# untitled.net
KiCad netlist of a schematic drawn in EAGLE
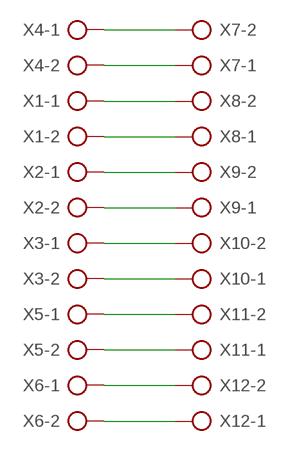
[diagram p0: schematic, sheet 1]

(export (version "E")
  (design (tool "Eeschema 10.0.6"))
  (components
    (comp (ref "X1")
      (value "AK500/2-H")
      (footprint "eagle-import:AK500_2-H")
      (libsource (lib "eagle-import") (part "AK500/2-H"))
    )
    (comp (ref "X2")
      (value "AK500/2-H")
      (footprint "eagle-import:AK500_2-H")
      (libsource (lib "eagle-import") (part "AK500/2-H"))
    )
    (comp (ref "X3")
      (value "AK500/2-H")
      (footprint "eagle-import:AK500_2-H")
      (libsource (lib "eagle-import") (part "AK500/2-H"))
    )
    (comp (ref "X4")
      (value "AK500/2-H")
      (footprint "eagle-import:AK500_2-H")
      (libsource (lib "eagle-import") (part "AK500/2-H"))
    )
    (comp (ref "X5")
      (value "AK500/2-H")
      (footprint "eagle-import:AK500_2-H")
      (libsource (lib "eagle-import") (part "AK500/2-H"))
    )
    (comp (ref "X6")
      (value "AK500/2-H")
      (footprint "eagle-import:AK500_2-H")
      (libsource (lib "eagle-import") (part "AK500/2-H"))
    )
    (comp (ref "X7")
      (value "AK500/2-H")
      (footprint "eagle-import:AK500_2-H")
      (libsource (lib "eagle-import") (part "AK500/2-H"))
    )
    (comp (ref "X8")
      (value "AK500/2-H")
      (footprint "eagle-import:AK500_2-H")
      (libsource (lib "eagle-import") (part "AK500/2-H"))
    )
    (comp (ref "X9")
      (value "AK500/2-H")
      (footprint "eagle-import:AK500_2-H")
      (libsource (lib "eagle-import") (part "AK500/2-H"))
    )
    (comp (ref "X10")
      (value "AK500/2-H")
      (footprint "eagle-import:AK500_2-H")
      (libsource (lib "eagle-import") (part "AK500/2-H"))
    )
    (comp (ref "X11")
      (value "AK500/2-H")
      (footprint "eagle-import:AK500_2-H")
      (libsource (lib "eagle-import") (part "AK500/2-H"))
    )
    (comp (ref "X12")
      (value "AK500/2-H")
      (footprint "eagle-import:AK500_2-H")
      (libsource (lib "eagle-import") (part "AK500/2-H"))
    )
  )
  (nets
    (net (code "1") (name "Net-(X1A-KL)") (class "Default")
      (node (ref "X1") (pin "1") (pinfunction "KL_1") (pintype "passive"))
      (node (ref "X8") (pin "2") (pinfunction "KL_2") (pintype "passive"))
    )
    (net (code "2") (name "Net-(X1B-KL)") (class "Default")
      (node (ref "X1") (pin "2") (pinfunction "KL_2") (pintype "passive"))
      (node (ref "X8") (pin "1") (pinfunction "KL_1") (pintype "passive"))
    )
    (net (code "3") (name "Net-(X2A-KL)") (class "Default")
      (node (ref "X2") (pin "1") (pinfunction "KL_1") (pintype "passive"))
      (node (ref "X9") (pin "2") (pinfunction "KL_2") (pintype "passive"))
    )
    (net (code "4") (name "Net-(X2B-KL)") (class "Default")
      (node (ref "X2") (pin "2") (pinfunction "KL_2") (pintype "passive"))
      (node (ref "X9") (pin "1") (pinfunction "KL_1") (pintype "passive"))
    )
    (net (code "5") (name "Net-(X4A-KL)") (class "Default")
      (node (ref "X4") (pin "1") (pinfunction "KL_1") (pintype "passive"))
      (node (ref "X7") (pin "2") (pinfunction "KL_2") (pintype "passive"))
    )
    (net (code "6") (name "Net-(X4B-KL)") (class "Default")
      (node (ref "X4") (pin "2") (pinfunction "KL_2") (pintype "passive"))
      (node (ref "X7") (pin "1") (pinfunction "KL_1") (pintype "passive"))
    )
    (net (code "7") (name "Net-(X10A-KL)") (class "Default")
      (node (ref "X10") (pin "1") (pinfunction "KL_1") (pintype "passive"))
      (node (ref "X3") (pin "2") (pinfunction "KL_2") (pintype "passive"))
    )
    (net (code "8") (name "Net-(X10B-KL)") (class "Default")
      (node (ref "X10") (pin "2") (pinfunction "KL_2") (pintype "passive"))
      (node (ref "X3") (pin "1") (pinfunction "KL_1") (pintype "passive"))
    )
    (net (code "9") (name "Net-(X11A-KL)") (class "Default")
      (node (ref "X11") (pin "1") (pinfunction "KL_1") (pintype "passive"))
      (node (ref "X5") (pin "2") (pinfunction "KL_2") (pintype "passive"))
    )
    (net (code "10") (name "Net-(X11B-KL)") (class "Default")
      (node (ref "X11") (pin "2") (pinfunction "KL_2") (pintype "passive"))
      (node (ref "X5") (pin "1") (pinfunction "KL_1") (pintype "passive"))
    )
    (net (code "11") (name "Net-(X12A-KL)") (class "Default")
      (node (ref "X12") (pin "1") (pinfunction "KL_1") (pintype "passive"))
      (node (ref "X6") (pin "2") (pinfunction "KL_2") (pintype "passive"))
    )
    (net (code "12") (name "Net-(X12B-KL)") (class "Default")
      (node (ref "X12") (pin "2") (pinfunction "KL_2") (pintype "passive"))
      (node (ref "X6") (pin "1") (pinfunction "KL_1") (pintype "passive"))
    )
  )
)
